# 4th_SCHEMATIC_EP.net
KiCad netlist of a schematic drawn in EAGLE
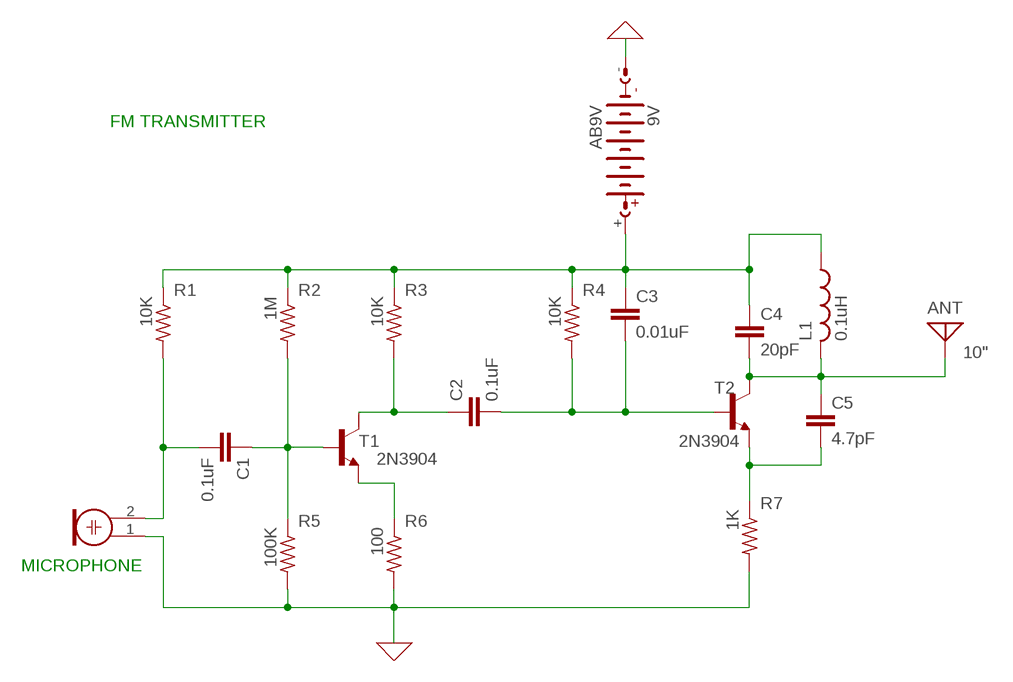
[diagram p0: schematic, sheet 1]

(export (version "E")
  (design (tool "Eeschema 10.0.6"))
  (components
    (comp (ref "9V")
      (value "AB9V")
      (footprint "eagle-import:AB9V")
      (libsource (lib "eagle-import") (part "AB9V"))
    )
    (comp (ref "ANT")
      (value "10\"")
      (footprint "eagle-import:PAD-01")
      (libsource (lib "eagle-import") (part "ANTENNA"))
    )
    (comp (ref "C1")
      (value "0.1uF")
      (footprint "eagle-import:C2.5-2")
      (libsource (lib "eagle-import") (part "C2.5/2"))
    )
    (comp (ref "C2")
      (value "0.1uF")
      (footprint "eagle-import:C2.5-2")
      (libsource (lib "eagle-import") (part "C2.5/2"))
    )
    (comp (ref "C3")
      (value "0.01uF")
      (footprint "eagle-import:C2.5-2")
      (libsource (lib "eagle-import") (part "C2.5/2"))
    )
    (comp (ref "C4")
      (value "20pF")
      (footprint "eagle-import:C2.5-2")
      (libsource (lib "eagle-import") (part "C2.5/2"))
    )
    (comp (ref "C5")
      (value "4.7pF")
      (footprint "eagle-import:C2.5-2")
      (libsource (lib "eagle-import") (part "C2.5/2"))
    )
    (comp (ref "L1")
      (value "0.1uH")
      (footprint "eagle-import:0207_7")
      (libsource (lib "eagle-import") (part "L-US0207/7"))
    )
    (comp (ref "MIC")
      (value "ELECTRET_MICROPHON-F6050AP")
      (footprint "eagle-import:F6050AP")
      (libsource (lib "eagle-import") (part "ELECTRET_MICROPHON-F6050AP"))
    )
    (comp (ref "R1")
      (value "10K")
      (footprint "eagle-import:R0603")
      (libsource (lib "eagle-import") (part "R-US_R0603"))
    )
    (comp (ref "R2")
      (value "1M")
      (footprint "eagle-import:R0603")
      (libsource (lib "eagle-import") (part "R-US_R0603"))
    )
    (comp (ref "R3")
      (value "10K")
      (footprint "eagle-import:R0603")
      (libsource (lib "eagle-import") (part "R-US_R0603"))
    )
    (comp (ref "R4")
      (value "10K")
      (footprint "eagle-import:R0603")
      (libsource (lib "eagle-import") (part "R-US_R0603"))
    )
    (comp (ref "R5")
      (value "100K")
      (footprint "eagle-import:R0603")
      (libsource (lib "eagle-import") (part "R-US_R0603"))
    )
    (comp (ref "R6")
      (value "100")
      (footprint "eagle-import:R0603")
      (libsource (lib "eagle-import") (part "R-US_R0603"))
    )
    (comp (ref "R7")
      (value "1K")
      (footprint "eagle-import:R0603")
      (libsource (lib "eagle-import") (part "R-US_R0603"))
    )
    (comp (ref "T1")
      (value "2N3904")
      (footprint "eagle-import:TO92")
      (libsource (lib "eagle-import") (part "2N3904"))
    )
    (comp (ref "T2")
      (value "2N3904")
      (footprint "eagle-import:TO92")
      (libsource (lib "eagle-import") (part "2N3904"))
    )
  )
  (nets
    (net (code "1") (name "GND") (class "Default")
      (node (ref "9V") (pin "-") (pinfunction "-_-") (pintype "passive"))
      (node (ref "MIC") (pin "1") (pinfunction "1_1") (pintype "passive"))
      (node (ref "R5") (pin "2") (pinfunction "2_2") (pintype "passive"))
      (node (ref "R6") (pin "2") (pinfunction "2_2") (pintype "passive"))
      (node (ref "R7") (pin "2") (pinfunction "2_2") (pintype "passive"))
    )
    (net (code "2") (name "Net-(9V-Pad+)") (class "Default")
      (node (ref "9V") (pin "+") (pinfunction "+_+") (pintype "passive"))
      (node (ref "C3") (pin "1") (pinfunction "1_1") (pintype "passive"))
      (node (ref "C4") (pin "1") (pinfunction "1_1") (pintype "passive"))
      (node (ref "L1") (pin "1") (pinfunction "1_1") (pintype "passive"))
      (node (ref "R1") (pin "1") (pinfunction "1_1") (pintype "passive"))
      (node (ref "R2") (pin "1") (pinfunction "1_1") (pintype "passive"))
      (node (ref "R3") (pin "1") (pinfunction "1_1") (pintype "passive"))
      (node (ref "R4") (pin "1") (pinfunction "1_1") (pintype "passive"))
    )
    (net (code "3") (name "Net-(C1-Pad2)") (class "Default")
      (node (ref "C1") (pin "2") (pinfunction "2_2") (pintype "passive"))
      (node (ref "MIC") (pin "2") (pinfunction "2_2") (pintype "passive"))
      (node (ref "R1") (pin "2") (pinfunction "2_2") (pintype "passive"))
    )
    (net (code "4") (name "Net-(T1-B)") (class "Default")
      (node (ref "C1") (pin "1") (pinfunction "1_1") (pintype "passive"))
      (node (ref "R2") (pin "2") (pinfunction "2_2") (pintype "passive"))
      (node (ref "R5") (pin "1") (pinfunction "1_1") (pintype "passive"))
      (node (ref "T1") (pin "2") (pinfunction "B_2") (pintype "passive"))
    )
    (net (code "5") (name "Net-(T1-C)") (class "Default")
      (node (ref "C2") (pin "1") (pinfunction "1_1") (pintype "passive"))
      (node (ref "R3") (pin "2") (pinfunction "2_2") (pintype "passive"))
      (node (ref "T1") (pin "1") (pinfunction "C_1") (pintype "passive"))
    )
    (net (code "6") (name "Net-(T1-E)") (class "Default")
      (node (ref "R6") (pin "1") (pinfunction "1_1") (pintype "passive"))
      (node (ref "T1") (pin "3") (pinfunction "E_3") (pintype "passive"))
    )
    (net (code "7") (name "Net-(T2-B)") (class "Default")
      (node (ref "C2") (pin "2") (pinfunction "2_2") (pintype "passive"))
      (node (ref "C3") (pin "2") (pinfunction "2_2") (pintype "passive"))
      (node (ref "R4") (pin "2") (pinfunction "2_2") (pintype "passive"))
      (node (ref "T2") (pin "2") (pinfunction "B_2") (pintype "passive"))
    )
    (net (code "8") (name "Net-(T2-C)") (class "Default")
      (node (ref "ANT") (pin "1") (pinfunction "1_1") (pintype "output"))
      (node (ref "C4") (pin "2") (pinfunction "2_2") (pintype "passive"))
      (node (ref "C5") (pin "1") (pinfunction "1_1") (pintype "passive"))
      (node (ref "L1") (pin "2") (pinfunction "2_2") (pintype "passive"))
      (node (ref "T2") (pin "1") (pinfunction "C_1") (pintype "passive"))
    )
    (net (code "9") (name "Net-(T2-E)") (class "Default")
      (node (ref "C5") (pin "2") (pinfunction "2_2") (pintype "passive"))
      (node (ref "R7") (pin "1") (pinfunction "1_1") (pintype "passive"))
      (node (ref "T2") (pin "3") (pinfunction "E_3") (pintype "passive"))
    )
  )
)
